# Mic_Speaker_Interconn.net
KiCad netlist of a schematic drawn in Altium Designer
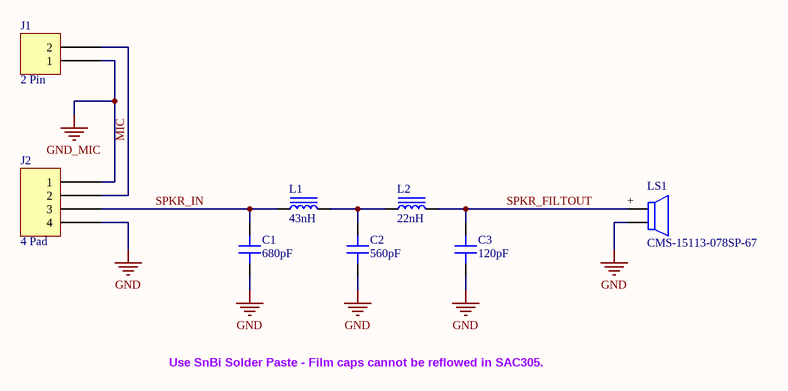
[diagram p0: Mic Speaker Interconn.SchDoc]

(export (version "E")
  (design (tool "Eeschema 10.0.6"))
  (components
    (comp (ref "C1")
      (value "680pF")
      (footprint "CAP FILM 0603_1608")
      (description "CAP FILM 680PF 2% 16VDC 0603")
      (fields
        (field (name "PART NUMBER") "ECH-U1C681GX5")
        (field (name "CAPACITANCE") "680pF")
        (field (name "MANUFACTURER") "Panasonic Electronic Components")
      )
      (libsource (lib "altiumlibrary.com") (part "Capacitor"))
    )
    (comp (ref "C2")
      (value "560pF")
      (footprint "CAP FILM 0603_1608")
      (description "CAP FILM 560PF 5% 16VDC 0603")
      (fields
        (field (name "PART NUMBER") "ECH-U1C561JX5")
        (field (name "CAPACITANCE") "560pF")
        (field (name "MANUFACTURER") "Panasonic Electronic Components")
      )
      (libsource (lib "altiumlibrary.com") (part "Capacitor"))
    )
    (comp (ref "C3")
      (value "120pF")
      (footprint "CAP FILM 0603_1608")
      (description "CAP FILM 120PF 5% 16VDC 0603")
      (fields
        (field (name "PART NUMBER") "ECH-U1C121JX5")
        (field (name "CAPACITANCE") "120pF")
        (field (name "MANUFACTURER") "Panasonic Electronic Components")
      )
      (libsource (lib "altiumlibrary.com") (part "Capacitor"))
    )
    (comp (ref "J1") (value "2 Pin") (footprint "Mic2Board") (libsource (lib "2 PIN") (part "2 Pin")))
    (comp (ref "J2") (value "4 Pad") (footprint "Wire2Board") (libsource (lib "4 PIN") (part "4 Pin")))
    (comp (ref "L1")
      (value "43nH")
      (footprint "IND 0603_1608 RF WW")
      (description "FIXED IND 43NH 840MA 210 MOHM")
      (fields
        (field (name "PART NUMBER") "LQW18AN43NJ8ZD")
        (field (name "MANUFACTURER") "Murata Electronics")
      )
      (libsource (lib "altiumlibrary.com") (part "Inductor"))
    )
    (comp (ref "L2")
      (value "22nH")
      (footprint "IND 0603_1608 RF WW")
      (description "FIXED IND 22NH 1.3A 86 MOHM")
      (fields
        (field (name "PART NUMBER") "LQW18AN22NG8ZD")
        (field (name "MANUFACTURER") "Murata Electronics")
      )
      (libsource (lib "altiumlibrary.com") (part "Inductor"))
    )
    (comp (ref "LS1")
      (value "CMS-15113-078SP-67")
      (footprint "CUI CMS-15113-078SP")
      (description "SPEAKER, 15 X 11 MM, 3 MM DEEP,")
      (fields (field (name "MANUFACTURER") "CUI Devices"))
      (libsource (lib "altiumlibrary.com") (part "SPEAKER 2 PIN"))
    )
  )
  (nets
    (net (code "1") (name "/MIC") (class "Default")
      (node (ref "J1") (pin "2") (pinfunction "2_2") (pintype "passive"))
      (node (ref "J2") (pin "2") (pinfunction "2_2") (pintype "passive"))
    )
    (net (code "2") (name "/SPKR_FILTOUT") (class "Default")
      (node (ref "C3") (pin "2") (pinfunction "2_2") (pintype "passive"))
      (node (ref "L2") (pin "2") (pinfunction "2_2") (pintype "passive"))
      (node (ref "LS1") (pin "+") (pinfunction "+_+") (pintype "passive"))
    )
    (net (code "3") (name "/SPKR_IN") (class "Default")
      (node (ref "C1") (pin "2") (pinfunction "2_2") (pintype "passive"))
      (node (ref "J2") (pin "3") (pinfunction "3_3") (pintype "passive"))
      (node (ref "L1") (pin "1") (pinfunction "1_1") (pintype "passive"))
    )
    (net (code "4") (name "GND") (class "Default")
      (node (ref "C1") (pin "1") (pinfunction "1_1") (pintype "passive"))
      (node (ref "C2") (pin "1") (pinfunction "1_1") (pintype "passive"))
      (node (ref "C3") (pin "1") (pinfunction "1_1") (pintype "passive"))
      (node (ref "J2") (pin "4") (pinfunction "4_4") (pintype "passive"))
      (node (ref "LS1") (pin "-") (pinfunction "-_-") (pintype "passive"))
    )
    (net (code "5") (name "GND_MIC") (class "Default")
      (node (ref "J1") (pin "1") (pinfunction "1_1") (pintype "passive"))
      (node (ref "J2") (pin "1") (pinfunction "1_1") (pintype "passive"))
    )
    (net (code "6") (name "Net-(C2-Pad2)") (class "Default")
      (node (ref "C2") (pin "2") (pinfunction "2_2") (pintype "passive"))
      (node (ref "L1") (pin "2") (pinfunction "2_2") (pintype "passive"))
      (node (ref "L2") (pin "1") (pinfunction "1_1") (pintype "passive"))
    )
  )
)
